# Measuring.net
KiCad netlist of a schematic drawn in Altium Designer
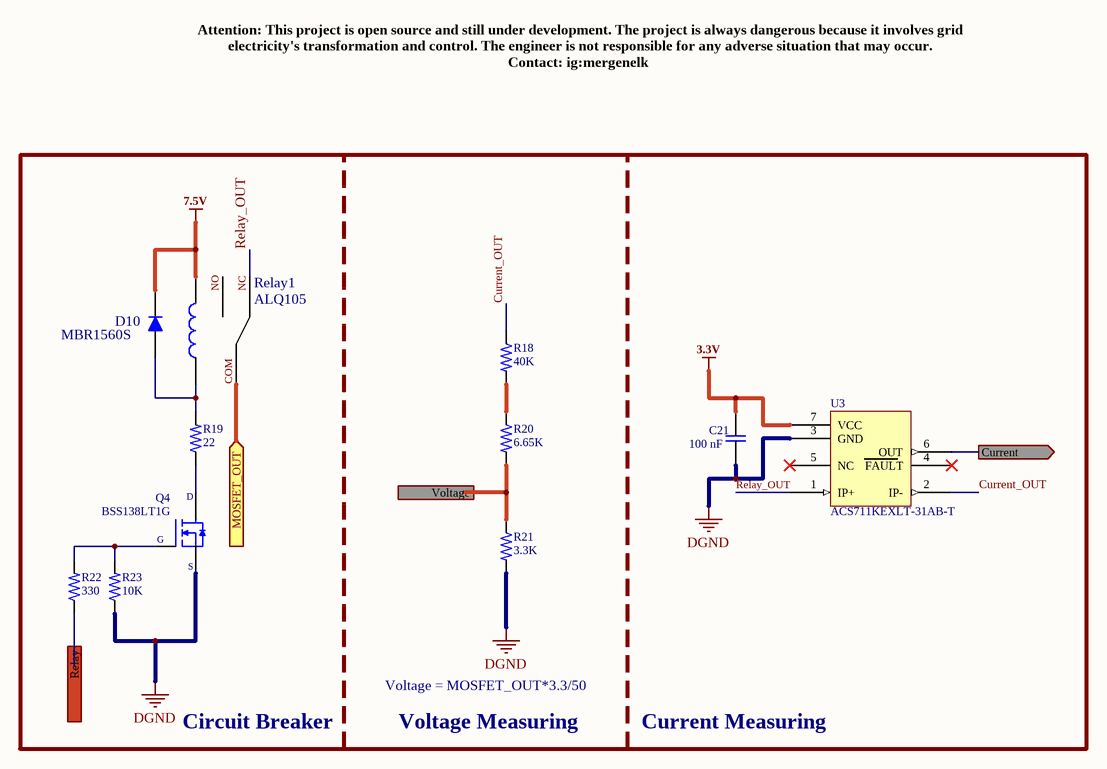
[diagram p0: Measuring.SchDoc]

(export (version "E")
  (design (tool "Eeschema 10.0.6"))
  (components
    (comp (ref "C21")
      (value "100 nF")
      (footprint "MergenElektronik_Capacitors_Ceramics_SMDs_0603_S_NS")
      (description "Mergen Elektronik - Capacitors - Ceramics - SMDs - 0603 - 100 nF - 16V")
      (fields (field (name "MANUFACTURER") "Samsung") (field (name "TOLERANCE") "±10%"))
      (libsource (lib "MergenElektronik_Capacitors_Ceramics_SMDs") (part "MergenElektronik_Capacitors_Ceramic_SMDs_100nF_16V"))
    )
    (comp (ref "D10")
      (value "MBR1560S")
      (footprint "MergenElektronik_Diodes_SingleDiodes_TO-277B")
      (description "Mergen Elektronik - Diodes - Single Diodes - MBR1560S")
      (fields (field (name "MANUFACTURER") "SMC Diode Solutions"))
      (libsource (lib "MergenElektronik_Diodes_SingleDiodes") (part "MergenElektronik_Diodes_SingleDiodes_MBR1560S"))
    )
    (comp (ref "Q4")
      (value "BSS138LT1G")
      (footprint "MergenElektronik_Transistors_Mosfets_SOT-23")
      (description "Mergen Elektronik - Transistors - Mosfets - BSS138LT1G")
      (fields (field (name "MANUFACTURER") "onsemi"))
      (libsource (lib "MergenElektronik_Transistors_Mosfets") (part "MergenElektronik_Transistors_Mosfets_BSS138LT1G"))
    )
    (comp (ref "R18")
      (value "40K")
      (footprint "MergenElektronik_Resistors_ChipResistors_0603_S_NS")
      (description "Mergen Elektronik - Resistors - Chip Resistors - 0603 - 40K")
      (fields (field (name "MANUFACTURER") "YAGEO") (field (name "POWER") "1/10W"))
      (libsource (lib "MergenElektronik_Resistors_ChipResistors") (part "MergenElektronik_Resistors_ChipResistors_0603_40K"))
    )
    (comp (ref "R19")
      (value "22")
      (footprint "MergenElektronik_Resistors_ChipResistors_0603_S")
      (description "Mergen Elektronik - Resistors - Chip Resistors - 0603 - 22")
      (fields (field (name "MANUFACTURER") "TE Connectivity") (field (name "POWER") "1/10W"))
      (libsource (lib "MergenElektronik_Resistors_ChipResistors") (part "MergenElektronik_Resistors_ChipResistors_0603_22"))
    )
    (comp (ref "R20")
      (value "6.65K")
      (footprint "MergenElektronik_Resistors_ChipResistors_0603_S_NS")
      (description "Mergen Elektronik - Resistors - Chip Resistors - 0603 - 6.65K")
      (fields (field (name "MANUFACTURER") "YAGEO") (field (name "POWER") "1/10W"))
      (libsource (lib "MergenElektronik_Resistors_ChipResistors") (part "MergenElektronik_Resistors_ChipResistors_0603_6.65K"))
    )
    (comp (ref "R21")
      (value "3.3K")
      (footprint "MergenElektronik_Resistors_ChipResistors_0603_S_NS")
      (description "Mergen Elektronik - Resistors - Chip Resistors - 0603 - 3.3K")
      (fields (field (name "MANUFACTURER") "YAGEO") (field (name "POWER") "1/10W"))
      (libsource (lib "MergenElektronik_Resistors_ChipResistors") (part "MergenElektronik_Resistors_ChipResistors_0603_3.3K"))
    )
    (comp (ref "R22")
      (value "330")
      (footprint "MergenElektronik_Resistors_ChipResistors_0603_S_NS")
      (description "Mergen Elektronik - Resistors - Chip Resistors - 0603 - 330R")
      (fields (field (name "MANUFACTURER") "Stackpole") (field (name "POWER") "1/10W"))
      (libsource (lib "MergenElektronik_Resistors_ChipResistors") (part "MergenElektronik_Resistors_ChipResistors_0603_330R"))
    )
    (comp (ref "R23")
      (value "10K")
      (footprint "MergenElektronik_Resistors_ChipResistors_0603_S_NS")
      (description "Mergen Elektronik - Resistors - Chip Resistors - 0603 - 10K")
      (fields (field (name "MANUFACTURER") "Stackpole") (field (name "POWER") "1/10W"))
      (libsource (lib "MergenElektronik_Resistors_ChipResistors") (part "MergenElektronik_Resistors_ChipResistors_0603_10K"))
    )
    (comp (ref "Relay1")
      (value "ALQ105")
      (footprint "MergenElektronik_Relays_PowerRelays_ALQ105")
      (description "Mergen Elektronik - Relays - Power Relays - ALQ105")
      (fields (field (name "MANUFACTURER") "Panasonic"))
      (libsource (lib "MergenElektronik_Relays_PowerRelays") (part "MergenElektronik_Relays_PowerRelays_ALQ105"))
    )
    (comp (ref "U3")
      (value "ACS711KEXLT-31AB-T")
      (footprint "MergenElektronik_Sensors_CurrentSensors_ACS711KEXLT-31AB-T")
      (description "Mergen Elektronik - Sensors - Current Sensors - ACS711KEXLT-31AB-T")
      (fields (field (name "MANUFACTURER") "Allegro MicroSystems"))
      (libsource (lib "MergenElektronik_Sensors_CurrentSensors") (part "MergenElektronik_Sensors_CurrentSensors_ACS711KEXLT-31AB-T"))
    )
  )
  (nets
    (net (code "1") (name "/Current") (class "Default")
      (node (ref "U3") (pin "6") (pinfunction "OUT_6") (pintype "output"))
    )
    (net (code "2") (name "/Current_OUT") (class "Default")
      (node (ref "R18") (pin "1") (pinfunction "1_1") (pintype "passive"))
      (node (ref "U3") (pin "2") (pinfunction "IP-_2") (pintype "output"))
    )
    (net (code "3") (name "/MOSFET_OUT") (class "Default")
      (node (ref "Relay1") (pin "COM") (pinfunction "COM_COM") (pintype "passive"))
    )
    (net (code "4") (name "/Relay") (class "Default")
      (node (ref "R22") (pin "1") (pinfunction "1_1") (pintype "passive"))
    )
    (net (code "5") (name "/Relay_OUT") (class "Default")
      (node (ref "Relay1") (pin "NC") (pinfunction "NC_NC") (pintype "passive"))
      (node (ref "U3") (pin "1") (pinfunction "IP+_1") (pintype "input"))
    )
    (net (code "6") (name "/Voltage") (class "Default")
      (node (ref "R20") (pin "2") (pinfunction "2_2") (pintype "passive"))
      (node (ref "R21") (pin "1") (pinfunction "1_1") (pintype "passive"))
    )
    (net (code "7") (name "3.3V") (class "Default")
      (node (ref "C21") (pin "1") (pinfunction "1_1") (pintype "passive"))
      (node (ref "U3") (pin "7") (pinfunction "VCC_7") (pintype "power_in"))
    )
    (net (code "8") (name "7.5V") (class "Default")
      (node (ref "D10") (pin "2") (pinfunction "KATOT_2") (pintype "passive"))
      (node (ref "Relay1") (pin "C2") (pinfunction "C2_C2") (pintype "passive"))
    )
    (net (code "9") (name "DGND") (class "Default")
      (node (ref "C21") (pin "2") (pinfunction "2_2") (pintype "passive"))
      (node (ref "Q4") (pin "2") (pinfunction "Source_2") (pintype "passive"))
      (node (ref "R21") (pin "2") (pinfunction "2_2") (pintype "passive"))
      (node (ref "R23") (pin "1") (pinfunction "1_1") (pintype "passive"))
      (node (ref "U3") (pin "3") (pinfunction "GND_3") (pintype "power_in"))
    )
    (net (code "10") (name "Net-(D10-ANOT)") (class "Default")
      (node (ref "D10") (pin "1") (pinfunction "ANOT_1") (pintype "passive"))
      (node (ref "R19") (pin "2") (pinfunction "2_2") (pintype "passive"))
      (node (ref "Relay1") (pin "C1") (pinfunction "C1_C1") (pintype "passive"))
    )
    (net (code "11") (name "Net-(Q4-Drain)") (class "Default")
      (node (ref "Q4") (pin "3") (pinfunction "Drain_3") (pintype "passive"))
      (node (ref "R19") (pin "1") (pinfunction "1_1") (pintype "passive"))
    )
    (net (code "12") (name "Net-(Q4-Gate)") (class "Default")
      (node (ref "Q4") (pin "1") (pinfunction "Gate_1") (pintype "passive"))
      (node (ref "R22") (pin "2") (pinfunction "2_2") (pintype "passive"))
      (node (ref "R23") (pin "2") (pinfunction "2_2") (pintype "passive"))
    )
    (net (code "13") (name "Net-(R18-Pad2)") (class "Default")
      (node (ref "R18") (pin "2") (pinfunction "2_2") (pintype "passive"))
      (node (ref "R20") (pin "1") (pinfunction "1_1") (pintype "passive"))
    )
    (net (code "14") (name "unconnected-(Relay1-PadNO)") (class "Default")
      (node (ref "Relay1") (pin "NO") (pinfunction "NO_NO") (pintype "passive"))
    )
    (net (code "15") (name "unconnected-(U3-FAULT-Pad4)") (class "Default")
      (node (ref "U3") (pin "4") (pinfunction "FAULT_4") (pintype "passive+no_connect"))
    )
    (net (code "16") (name "unconnected-(U3-NC-Pad5)") (class "Default")
      (node (ref "U3") (pin "5") (pinfunction "NC_5") (pintype "passive+no_connect"))
    )
  )
)
